# tinyx_core_v0.net
KiCad netlist of a schematic drawn in EAGLE
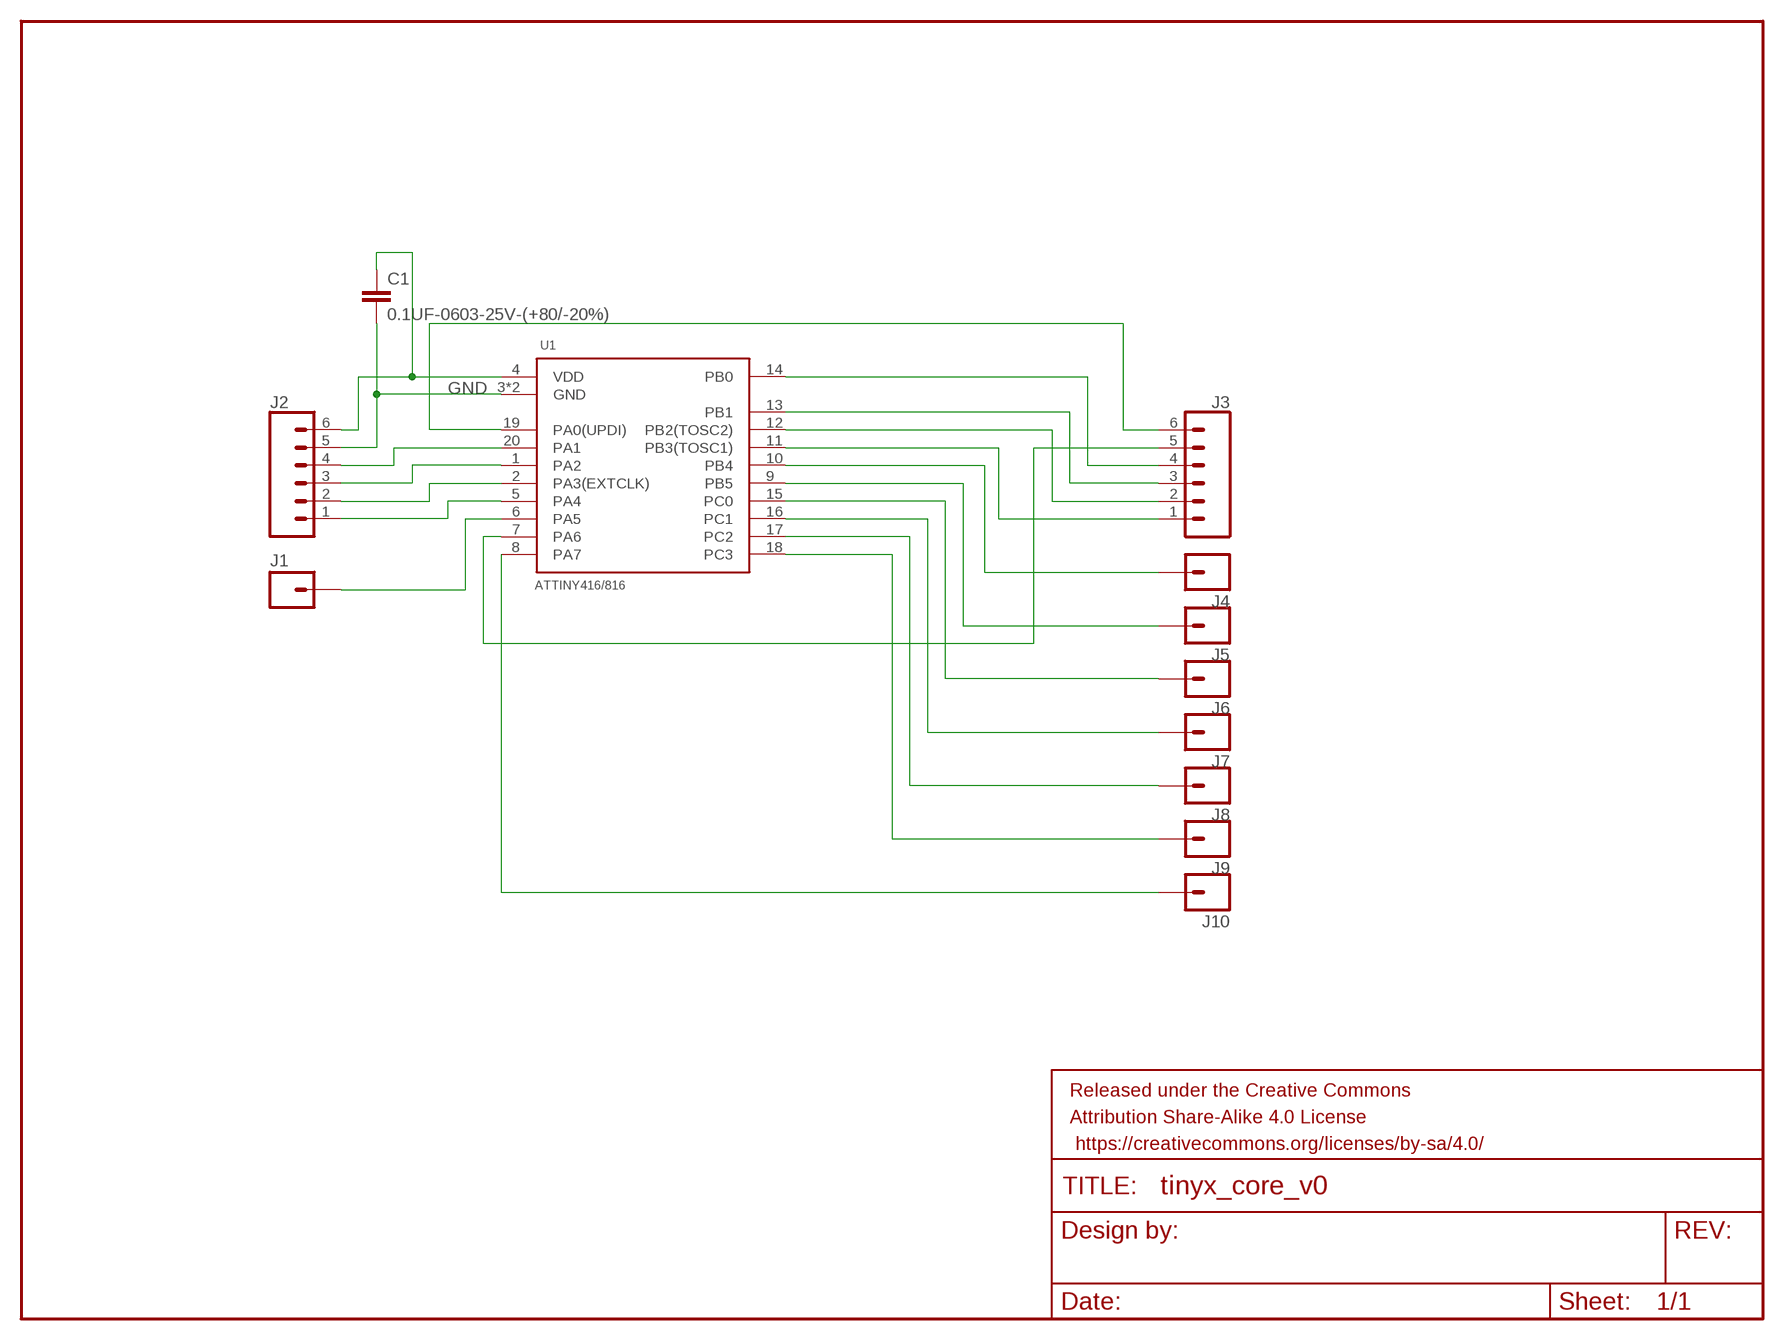
[diagram p0: schematic, sheet 1]

(export (version "E")
  (design (tool "Eeschema 10.0.6"))
  (components
    (comp (ref "C1")
      (value "0.1UF-0603-25V-(+80/-20%)")
      (footprint "eagle-import:0603")
      (libsource (lib "eagle-import") (part "0.1UF-0603-25V-(+80/-20%)"))
    )
    (comp (ref "FRAME1")
      (value "FRAME-LETTER")
      (footprint "eagle-import:CREATIVE_COMMONS")
      (libsource (lib "eagle-import") (part "FRAME-LETTER"))
    )
    (comp (ref "J1")
      (value "M01TINY")
      (footprint "eagle-import:1X01_TINY")
      (libsource (lib "eagle-import") (part "M01TINY"))
    )
    (comp (ref "J2")
      (value "CONN_06NO_SILK_FEMALE_PTH")
      (footprint "eagle-import:1X06_NO_SILK")
      (libsource (lib "eagle-import") (part "CONN_06NO_SILK_FEMALE_PTH"))
    )
    (comp (ref "J3")
      (value "CONN_06NO_SILK_FEMALE_PTH")
      (footprint "eagle-import:1X06_NO_SILK")
      (libsource (lib "eagle-import") (part "CONN_06NO_SILK_FEMALE_PTH"))
    )
    (comp (ref "J4")
      (value "M01TINY")
      (footprint "eagle-import:1X01_TINY")
      (libsource (lib "eagle-import") (part "M01TINY"))
    )
    (comp (ref "J5")
      (value "M01TINY")
      (footprint "eagle-import:1X01_TINY")
      (libsource (lib "eagle-import") (part "M01TINY"))
    )
    (comp (ref "J6")
      (value "M01TINY")
      (footprint "eagle-import:1X01_TINY")
      (libsource (lib "eagle-import") (part "M01TINY"))
    )
    (comp (ref "J7")
      (value "M01TINY")
      (footprint "eagle-import:1X01_TINY")
      (libsource (lib "eagle-import") (part "M01TINY"))
    )
    (comp (ref "J8")
      (value "M01TINY")
      (footprint "eagle-import:1X01_TINY")
      (libsource (lib "eagle-import") (part "M01TINY"))
    )
    (comp (ref "J9")
      (value "M01TINY")
      (footprint "eagle-import:1X01_TINY")
      (libsource (lib "eagle-import") (part "M01TINY"))
    )
    (comp (ref "J10")
      (value "M01TINY")
      (footprint "eagle-import:1X01_TINY")
      (libsource (lib "eagle-import") (part "M01TINY"))
    )
    (comp (ref "U1")
      (value "ATTINY416/816")
      (footprint "eagle-import:VQFN-20")
      (libsource (lib "eagle-import") (part "ATTINY416/816"))
    )
  )
  (nets
    (net (code "1") (name "/GND") (class "Default")
      (node (ref "C1") (pin "2") (pinfunction "2_2") (pintype "passive"))
      (node (ref "J2") (pin "5") (pinfunction "5_5") (pintype "passive"))
      (node (ref "U1") (pin "3") (pinfunction "GND_3") (pintype "bidirectional"))
      (node (ref "U1") (pin "EXP") (pinfunction "GND_EXP") (pintype "bidirectional"))
    )
    (net (code "2") (name "Net-(J1-1)") (class "Default")
      (node (ref "J1") (pin "P$1") (pinfunction "1_P$1") (pintype "passive"))
      (node (ref "U1") (pin "6") (pinfunction "PA5_6") (pintype "bidirectional"))
    )
    (net (code "3") (name "Net-(J4-1)") (class "Default")
      (node (ref "J4") (pin "P$1") (pinfunction "1_P$1") (pintype "passive"))
      (node (ref "U1") (pin "10") (pinfunction "PB4_10") (pintype "bidirectional"))
    )
    (net (code "4") (name "Net-(J5-1)") (class "Default")
      (node (ref "J5") (pin "P$1") (pinfunction "1_P$1") (pintype "passive"))
      (node (ref "U1") (pin "9") (pinfunction "PB5_9") (pintype "bidirectional"))
    )
    (net (code "5") (name "Net-(J6-1)") (class "Default")
      (node (ref "J6") (pin "P$1") (pinfunction "1_P$1") (pintype "passive"))
      (node (ref "U1") (pin "15") (pinfunction "PC0_15") (pintype "bidirectional"))
    )
    (net (code "6") (name "Net-(J7-1)") (class "Default")
      (node (ref "J7") (pin "P$1") (pinfunction "1_P$1") (pintype "passive"))
      (node (ref "U1") (pin "16") (pinfunction "PC1_16") (pintype "bidirectional"))
    )
    (net (code "7") (name "Net-(J8-1)") (class "Default")
      (node (ref "J8") (pin "P$1") (pinfunction "1_P$1") (pintype "passive"))
      (node (ref "U1") (pin "17") (pinfunction "PC2_17") (pintype "bidirectional"))
    )
    (net (code "8") (name "Net-(J9-1)") (class "Default")
      (node (ref "J9") (pin "P$1") (pinfunction "1_P$1") (pintype "passive"))
      (node (ref "U1") (pin "18") (pinfunction "PC3_18") (pintype "bidirectional"))
    )
    (net (code "9") (name "Net-(J10-1)") (class "Default")
      (node (ref "J10") (pin "P$1") (pinfunction "1_P$1") (pintype "passive"))
      (node (ref "U1") (pin "8") (pinfunction "PA7_8") (pintype "bidirectional"))
    )
    (net (code "10") (name "Net-(U1-PA0(UPDI))") (class "Default")
      (node (ref "J3") (pin "6") (pinfunction "6_6") (pintype "passive"))
      (node (ref "U1") (pin "19") (pinfunction "PA0(UPDI)_19") (pintype "bidirectional"))
    )
    (net (code "11") (name "Net-(U1-PA1)") (class "Default")
      (node (ref "J2") (pin "4") (pinfunction "4_4") (pintype "passive"))
      (node (ref "U1") (pin "20") (pinfunction "PA1_20") (pintype "bidirectional"))
    )
    (net (code "12") (name "Net-(U1-PA2)") (class "Default")
      (node (ref "J2") (pin "3") (pinfunction "3_3") (pintype "passive"))
      (node (ref "U1") (pin "1") (pinfunction "PA2_1") (pintype "bidirectional"))
    )
    (net (code "13") (name "Net-(U1-PA3(EXTCLK))") (class "Default")
      (node (ref "J2") (pin "2") (pinfunction "2_2") (pintype "passive"))
      (node (ref "U1") (pin "2") (pinfunction "PA3(EXTCLK)_2") (pintype "bidirectional"))
    )
    (net (code "14") (name "Net-(U1-PA4)") (class "Default")
      (node (ref "J2") (pin "1") (pinfunction "1_1") (pintype "passive"))
      (node (ref "U1") (pin "5") (pinfunction "PA4_5") (pintype "bidirectional"))
    )
    (net (code "15") (name "Net-(U1-PA6)") (class "Default")
      (node (ref "J3") (pin "5") (pinfunction "5_5") (pintype "passive"))
      (node (ref "U1") (pin "7") (pinfunction "PA6_7") (pintype "bidirectional"))
    )
    (net (code "16") (name "Net-(U1-PB0)") (class "Default")
      (node (ref "J3") (pin "4") (pinfunction "4_4") (pintype "passive"))
      (node (ref "U1") (pin "14") (pinfunction "PB0_14") (pintype "bidirectional"))
    )
    (net (code "17") (name "Net-(U1-PB1)") (class "Default")
      (node (ref "J3") (pin "3") (pinfunction "3_3") (pintype "passive"))
      (node (ref "U1") (pin "13") (pinfunction "PB1_13") (pintype "bidirectional"))
    )
    (net (code "18") (name "Net-(U1-PB2(TOSC2))") (class "Default")
      (node (ref "J3") (pin "2") (pinfunction "2_2") (pintype "passive"))
      (node (ref "U1") (pin "12") (pinfunction "PB2(TOSC2)_12") (pintype "bidirectional"))
    )
    (net (code "19") (name "Net-(U1-PB3(TOSC1))") (class "Default")
      (node (ref "J3") (pin "1") (pinfunction "1_1") (pintype "passive"))
      (node (ref "U1") (pin "11") (pinfunction "PB3(TOSC1)_11") (pintype "bidirectional"))
    )
    (net (code "20") (name "Net-(U1-VDD)") (class "Default")
      (node (ref "C1") (pin "1") (pinfunction "1_1") (pintype "passive"))
      (node (ref "J2") (pin "6") (pinfunction "6_6") (pintype "passive"))
      (node (ref "U1") (pin "4") (pinfunction "VDD_4") (pintype "bidirectional"))
    )
  )
)
